# OTGW01_opentherm_rev1.net
KiCad netlist of a schematic drawn in Altium Designer
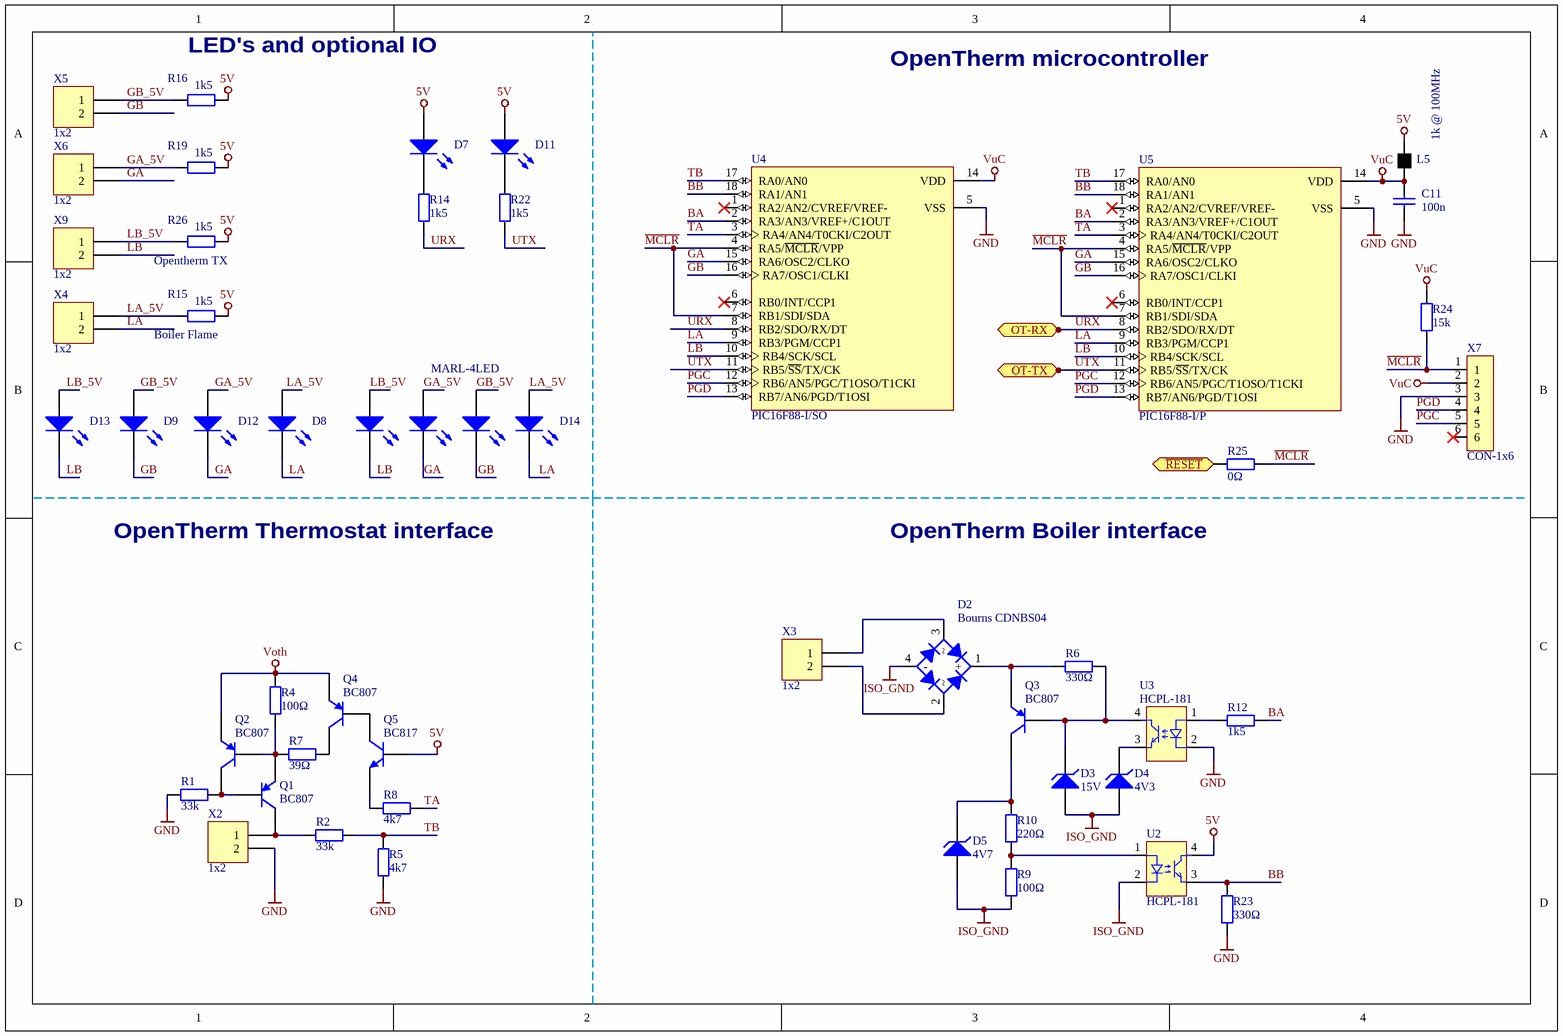
[diagram p0: OTGW01_opentherm_rev1.SchDoc]

(export (version "E")
  (design (tool "Eeschema 10.0.6"))
  (components
    (comp (ref "C11")
      (value "100n")
      (footprint "0805")
      (description "Capacitor Non Polarized")
      (libsource (lib "sap") (part "C"))
    )
    (comp (ref "D2")
      (value "Bourns CDNBS04")
      (footprint "SOD-106")
      (description "Full Wave Diode Bridge")
      (libsource (lib "OTGW01_rev1") (part "Bridge"))
    )
    (comp (ref "D3")
      (value "15V")
      (footprint "SOD123")
      (description "Zener Diode")
      (libsource (lib "OTGW01_rev1") (part "D_Z"))
    )
    (comp (ref "D4")
      (value "4V3")
      (footprint "SOD123")
      (description "Zener Diode")
      (libsource (lib "OTGW01_rev1") (part "D_Z"))
    )
    (comp (ref "D5")
      (value "4V7")
      (footprint "SOD123")
      (description "Zener Diode")
      (libsource (lib "OTGW01_rev1") (part "D_Z"))
    )
    (comp (ref "D7")
      (value "PLCC2 LED")
      (footprint "PLCC2")
      (description "LED")
      (libsource (lib "OTGW01_rev1") (part "LED"))
    )
    (comp (ref "D8")
      (value "PLCC2 LED")
      (footprint "PLCC2")
      (description "LED")
      (libsource (lib "OTGW01_rev1") (part "LED"))
    )
    (comp (ref "D9")
      (value "PLCC2 LED")
      (footprint "PLCC2")
      (description "LED")
      (libsource (lib "OTGW01_rev1") (part "LED"))
    )
    (comp (ref "D11")
      (value "PLCC2 LED")
      (footprint "PLCC2")
      (description "LED")
      (libsource (lib "OTGW01_rev1") (part "LED"))
    )
    (comp (ref "D12")
      (value "PLCC2 LED")
      (footprint "PLCC2")
      (description "LED")
      (libsource (lib "OTGW01_rev1") (part "LED"))
    )
    (comp (ref "D13")
      (value "PLCC2 LED")
      (footprint "PLCC2")
      (description "LED")
      (libsource (lib "OTGW01_rev1") (part "LED"))
    )
    (comp (ref "D14")
      (value "MARL-4LED")
      (footprint "MARL-4LED")
      (libsource (lib "OTGW01_rev1") (part "MARL-4LED"))
    )
    (comp (ref "L5")
      (value "1k @ 100MHz")
      (footprint "0805")
      (libsource (lib "OTGW01_rev1") (part "Ferrite"))
    )
    (comp (ref "Q1")
      (value "BC807")
      (footprint "SOT23")
      (description "PNP Medium Power Transistor")
      (libsource (lib "OTGW01_rev1") (part "PNP"))
    )
    (comp (ref "Q2")
      (value "BC807")
      (footprint "SOT23")
      (description "PNP Medium Power Transistor")
      (libsource (lib "OTGW01_rev1") (part "PNP"))
    )
    (comp (ref "Q3")
      (value "BC807")
      (footprint "SOT23")
      (description "PNP Medium Power Transistor")
      (libsource (lib "OTGW01_rev1") (part "PNP"))
    )
    (comp (ref "Q4")
      (value "BC807")
      (footprint "SOT23")
      (description "PNP Medium Power Transistor")
      (libsource (lib "OTGW01_rev1") (part "PNP"))
    )
    (comp (ref "Q5")
      (value "BC817")
      (footprint "SOT23")
      (description "NPN Medium Power Transistor")
      (libsource (lib "OTGW01_rev1") (part "NPN"))
    )
    (comp (ref "R1")
      (value "33k")
      (footprint "0805")
      (description "Resistor")
      (libsource (lib "OTGW01_rev1") (part "R"))
    )
    (comp (ref "R2")
      (value "33k")
      (footprint "0805")
      (description "Resistor")
      (libsource (lib "OTGW01_rev1") (part "R"))
    )
    (comp (ref "R4")
      (value "100Ω")
      (footprint "0805")
      (description "Resistor")
      (libsource (lib "") (part "R_2"))
    )
    (comp (ref "R5")
      (value "4k7")
      (footprint "0805")
      (description "Resistor")
      (libsource (lib "") (part "R_2"))
    )
    (comp (ref "R6")
      (value "330Ω")
      (footprint "0805")
      (description "Resistor")
      (libsource (lib "") (part "R_3"))
    )
    (comp (ref "R7")
      (value "39Ω")
      (footprint "0805")
      (description "Resistor")
      (libsource (lib "OTGW01_rev1") (part "R"))
    )
    (comp (ref "R8")
      (value "4k7")
      (footprint "0805")
      (description "Resistor")
      (libsource (lib "OTGW01_rev1") (part "R"))
    )
    (comp (ref "R9")
      (value "100Ω")
      (footprint "0805")
      (description "Resistor")
      (libsource (lib "") (part "R_1"))
    )
    (comp (ref "R10")
      (value "220Ω")
      (footprint "0805")
      (description "Resistor")
      (libsource (lib "") (part "R_1"))
    )
    (comp (ref "R12")
      (value "1k5")
      (footprint "0805")
      (description "Resistor")
      (libsource (lib "") (part "R_3"))
    )
    (comp (ref "R14")
      (value "1k5")
      (footprint "0805")
      (description "Resistor")
      (libsource (lib "") (part "R_2"))
    )
    (comp (ref "R15")
      (value "1k5")
      (footprint "0805")
      (description "Resistor")
      (libsource (lib "OTGW01_rev1") (part "R"))
    )
    (comp (ref "R16")
      (value "1k5")
      (footprint "0805")
      (description "Resistor")
      (libsource (lib "OTGW01_rev1") (part "R"))
    )
    (comp (ref "R19")
      (value "1k5")
      (footprint "0805")
      (description "Resistor")
      (libsource (lib "OTGW01_rev1") (part "R"))
    )
    (comp (ref "R22")
      (value "1k5")
      (footprint "0805")
      (description "Resistor")
      (libsource (lib "") (part "R_2"))
    )
    (comp (ref "R23")
      (value "330Ω")
      (footprint "0805")
      (description "Resistor")
      (libsource (lib "") (part "R_1"))
    )
    (comp (ref "R24")
      (value "15k")
      (footprint "0805")
      (description "Resistor")
      (libsource (lib "") (part "R_1"))
    )
    (comp (ref "R25")
      (value "0Ω")
      (footprint "0805")
      (description "Resistor")
      (libsource (lib "OTGW01_rev1") (part "R"))
    )
    (comp (ref "R26")
      (value "1k5")
      (footprint "0805")
      (description "Resistor")
      (libsource (lib "OTGW01_rev1") (part "R"))
    )
    (comp (ref "U2")
      (value "HCPL-181")
      (footprint "HCPL-181")
      (libsource (lib "OTGW01_rev1") (part "HCPL-181"))
    )
    (comp (ref "U3") (value "HCPL-181") (footprint "HCPL-181") (libsource (lib "") (part "HCPL-181_1")))
    (comp (ref "U4")
      (value "PIC16F88-I/SO")
      (footprint "SOIC18")
      (libsource (lib "OTGW01_rev1") (part "MC-8B-16F88-IL18"))
    )
    (comp (ref "U5")
      (value "PIC16F88-I/P")
      (footprint "PDIP300-P18")
      (libsource (lib "OTGW01_rev1") (part "MC-8B-16F88-IL18"))
    )
    (comp (ref "X2")
      (value "1x2")
      (footprint "Terminal_2x3.5mm")
      (libsource (lib "OTGW01_rev1") (part "CON_1x2"))
    )
    (comp (ref "X3")
      (value "1x2")
      (footprint "Terminal_2x3.5mm")
      (libsource (lib "OTGW01_rev1") (part "CON_1x2"))
    )
    (comp (ref "X4")
      (value "1x2")
      (footprint "Terminal_2x3.5mm")
      (libsource (lib "OTGW01_rev1") (part "CON_1x2"))
    )
    (comp (ref "X5")
      (value "1x2")
      (footprint "Terminal_2x3.5mm")
      (libsource (lib "OTGW01_rev1") (part "CON_1x2"))
    )
    (comp (ref "X6")
      (value "1x2")
      (footprint "Terminal_2x3.5mm")
      (libsource (lib "OTGW01_rev1") (part "CON_1x2"))
    )
    (comp (ref "X7")
      (value "CON-1x6")
      (footprint "SIL-1x6-2.54")
      (libsource (lib "OTGW01_rev1") (part "CON-1x6"))
    )
    (comp (ref "X9")
      (value "1x2")
      (footprint "Terminal_2x3.5mm")
      (libsource (lib "OTGW01_rev1") (part "CON_1x2"))
    )
  )
  (nets
    (net (code "1") (name "/BA") (class "Default")
      (node (ref "R12") (pin "1") (pinfunction "1_1") (pintype "passive"))
      (node (ref "U4") (pin "2") (pinfunction "RA3/AN3/VREF+/C1OUT_2") (pintype "bidirectional"))
      (node (ref "U5") (pin "2") (pinfunction "RA3/AN3/VREF+/C1OUT_2") (pintype "bidirectional"))
    )
    (net (code "2") (name "/BB") (class "Default")
      (node (ref "R23") (pin "1") (pinfunction "1_1") (pintype "passive"))
      (node (ref "U2") (pin "3") (pinfunction "C_3") (pintype "passive"))
      (node (ref "U4") (pin "18") (pinfunction "RA1/AN1_18") (pintype "bidirectional"))
      (node (ref "U5") (pin "18") (pinfunction "RA1/AN1_18") (pintype "bidirectional"))
    )
    (net (code "3") (name "/GA") (class "Default")
      (node (ref "D12") (pin "2") (pinfunction "K_2") (pintype "passive"))
      (node (ref "D14") (pin "6") (pinfunction "K_6") (pintype "passive"))
      (node (ref "U4") (pin "15") (pinfunction "RA6/OSC2/CLKO_15") (pintype "bidirectional"))
      (node (ref "U5") (pin "15") (pinfunction "RA6/OSC2/CLKO_15") (pintype "bidirectional"))
      (node (ref "X6") (pin "2") (pinfunction "2_2") (pintype "passive"))
    )
    (net (code "4") (name "/GA_5V") (class "Default")
      (node (ref "D12") (pin "1") (pinfunction "A_1") (pintype "passive"))
      (node (ref "D14") (pin "5") (pinfunction "A_5") (pintype "passive"))
      (node (ref "R19") (pin "1") (pinfunction "1_1") (pintype "passive"))
      (node (ref "X6") (pin "1") (pinfunction "1_1") (pintype "passive"))
    )
    (net (code "5") (name "/GB") (class "Default")
      (node (ref "D14") (pin "4") (pinfunction "K_4") (pintype "passive"))
      (node (ref "D9") (pin "2") (pinfunction "K_2") (pintype "passive"))
      (node (ref "U4") (pin "16") (pinfunction "RA7/OSC1/CLKI_16") (pintype "bidirectional"))
      (node (ref "U5") (pin "16") (pinfunction "RA7/OSC1/CLKI_16") (pintype "bidirectional"))
      (node (ref "X5") (pin "2") (pinfunction "2_2") (pintype "passive"))
    )
    (net (code "6") (name "/GB_5V") (class "Default")
      (node (ref "D14") (pin "3") (pinfunction "A_3") (pintype "passive"))
      (node (ref "D9") (pin "1") (pinfunction "A_1") (pintype "passive"))
      (node (ref "R16") (pin "1") (pinfunction "1_1") (pintype "passive"))
      (node (ref "X5") (pin "1") (pinfunction "1_1") (pintype "passive"))
    )
    (net (code "7") (name "/LA") (class "Default")
      (node (ref "D14") (pin "2") (pinfunction "K_2") (pintype "passive"))
      (node (ref "D8") (pin "2") (pinfunction "K_2") (pintype "passive"))
      (node (ref "U4") (pin "9") (pinfunction "RB3/PGM/CCP1_9") (pintype "bidirectional"))
      (node (ref "U5") (pin "9") (pinfunction "RB3/PGM/CCP1_9") (pintype "bidirectional"))
      (node (ref "X4") (pin "2") (pinfunction "2_2") (pintype "passive"))
    )
    (net (code "8") (name "/LA_5V") (class "Default")
      (node (ref "D14") (pin "1") (pinfunction "A_1") (pintype "passive"))
      (node (ref "D8") (pin "1") (pinfunction "A_1") (pintype "passive"))
      (node (ref "R15") (pin "1") (pinfunction "1_1") (pintype "passive"))
      (node (ref "X4") (pin "1") (pinfunction "1_1") (pintype "passive"))
    )
    (net (code "9") (name "/LB") (class "Default")
      (node (ref "D13") (pin "2") (pinfunction "K_2") (pintype "passive"))
      (node (ref "D14") (pin "8") (pinfunction "K_8") (pintype "passive"))
      (node (ref "U4") (pin "10") (pinfunction "RB4/SCK/SCL_10") (pintype "bidirectional"))
      (node (ref "U5") (pin "10") (pinfunction "RB4/SCK/SCL_10") (pintype "bidirectional"))
      (node (ref "X9") (pin "2") (pinfunction "2_2") (pintype "passive"))
    )
    (net (code "10") (name "/LB_5V") (class "Default")
      (node (ref "D13") (pin "1") (pinfunction "A_1") (pintype "passive"))
      (node (ref "D14") (pin "7") (pinfunction "A_7") (pintype "passive"))
      (node (ref "R26") (pin "1") (pinfunction "1_1") (pintype "passive"))
      (node (ref "X9") (pin "1") (pinfunction "1_1") (pintype "passive"))
    )
    (net (code "11") (name "/PGC") (class "Default")
      (node (ref "U4") (pin "12") (pinfunction "RB6/AN5/PGC/T1OSO/T1CKI_12") (pintype "bidirectional"))
      (node (ref "U5") (pin "12") (pinfunction "RB6/AN5/PGC/T1OSO/T1CKI_12") (pintype "bidirectional"))
      (node (ref "X7") (pin "5") (pinfunction "5_5") (pintype "passive"))
    )
    (net (code "12") (name "/PGD") (class "Default")
      (node (ref "U4") (pin "13") (pinfunction "RB7/AN6/PGD/T1OSI_13") (pintype "bidirectional"))
      (node (ref "U5") (pin "13") (pinfunction "RB7/AN6/PGD/T1OSI_13") (pintype "bidirectional"))
      (node (ref "X7") (pin "4") (pinfunction "4_4") (pintype "passive"))
    )
    (net (code "13") (name "/TA") (class "Default")
      (node (ref "R8") (pin "2") (pinfunction "2_2") (pintype "passive"))
      (node (ref "U4") (pin "3") (pinfunction "RA4/AN4/T0CKI/C2OUT_3") (pintype "bidirectional"))
      (node (ref "U5") (pin "3") (pinfunction "RA4/AN4/T0CKI/C2OUT_3") (pintype "bidirectional"))
    )
    (net (code "14") (name "/TB") (class "Default")
      (node (ref "R2") (pin "2") (pinfunction "2_2") (pintype "passive"))
      (node (ref "R5") (pin "2") (pinfunction "2_2") (pintype "passive"))
      (node (ref "U4") (pin "17") (pinfunction "RA0/AN0_17") (pintype "bidirectional"))
      (node (ref "U5") (pin "17") (pinfunction "RA0/AN0_17") (pintype "bidirectional"))
    )
    (net (code "15") (name "/URX") (class "Default")
      (node (ref "R14") (pin "1") (pinfunction "1_1") (pintype "passive"))
      (node (ref "U4") (pin "8") (pinfunction "RB2/SDO/RX/DT_8") (pintype "bidirectional"))
      (node (ref "U5") (pin "8") (pinfunction "RB2/SDO/RX/DT_8") (pintype "bidirectional"))
    )
    (net (code "16") (name "/UTX") (class "Default")
      (node (ref "R22") (pin "1") (pinfunction "1_1") (pintype "passive"))
      (node (ref "U4") (pin "11") (pinfunction "RB5/~{SS}/TX/CK_11") (pintype "bidirectional"))
      (node (ref "U5") (pin "11") (pinfunction "RB5/~{SS}/TX/CK_11") (pintype "bidirectional"))
    )
    (net (code "17") (name "/~{MCLR}") (class "Default")
      (node (ref "R24") (pin "2") (pinfunction "2_2") (pintype "passive"))
      (node (ref "R25") (pin "2") (pinfunction "2_2") (pintype "passive"))
      (node (ref "U4") (pin "4") (pinfunction "RA5/~{MCLR}/VPP_4") (pintype "bidirectional"))
      (node (ref "U4") (pin "7") (pinfunction "RB1/SDI/SDA_7") (pintype "bidirectional"))
      (node (ref "U5") (pin "4") (pinfunction "RA5/~{MCLR}/VPP_4") (pintype "bidirectional"))
      (node (ref "U5") (pin "7") (pinfunction "RB1/SDI/SDA_7") (pintype "bidirectional"))
      (node (ref "X7") (pin "1") (pinfunction "1_1") (pintype "passive"))
    )
    (net (code "18") (name "/~{RESET}") (class "Default")
      (node (ref "R25") (pin "1") (pinfunction "1_1") (pintype "passive"))
    )
    (net (code "19") (name "5V") (class "Default")
      (node (ref "D11") (pin "1") (pinfunction "A_1") (pintype "passive"))
      (node (ref "D7") (pin "1") (pinfunction "A_1") (pintype "passive"))
      (node (ref "L5") (pin "2") (pinfunction "OUT_2") (pintype "passive"))
      (node (ref "Q5") (pin "3") (pinfunction "B_3") (pintype "passive"))
      (node (ref "R15") (pin "2") (pinfunction "2_2") (pintype "passive"))
      (node (ref "R16") (pin "2") (pinfunction "2_2") (pintype "passive"))
      (node (ref "R19") (pin "2") (pinfunction "2_2") (pintype "passive"))
      (node (ref "R26") (pin "2") (pinfunction "2_2") (pintype "passive"))
      (node (ref "U2") (pin "4") (pinfunction "D_4") (pintype "passive"))
    )
    (net (code "20") (name "GND") (class "Default")
      (node (ref "C11") (pin "1") (pinfunction "1_1") (pintype "passive"))
      (node (ref "R1") (pin "1") (pinfunction "1_1") (pintype "passive"))
      (node (ref "R23") (pin "2") (pinfunction "2_2") (pintype "passive"))
      (node (ref "R5") (pin "1") (pinfunction "1_1") (pintype "passive"))
      (node (ref "U3") (pin "2") (pinfunction "B_2") (pintype "passive"))
      (node (ref "U4") (pin "5") (pinfunction "VSS_5") (pintype "power_in"))
      (node (ref "U5") (pin "5") (pinfunction "VSS_5") (pintype "power_in"))
      (node (ref "X2") (pin "2") (pinfunction "2_2") (pintype "passive"))
      (node (ref "X7") (pin "3") (pinfunction "3_3") (pintype "passive"))
    )
    (net (code "21") (name "ISO_GND") (class "Default")
      (node (ref "D2") (pin "4") (pinfunction "-_4") (pintype "passive"))
      (node (ref "D3") (pin "2") (pinfunction "Anode_2") (pintype "passive"))
      (node (ref "D4") (pin "2") (pinfunction "Anode_2") (pintype "passive"))
      (node (ref "D5") (pin "2") (pinfunction "Anode_2") (pintype "passive"))
      (node (ref "R9") (pin "2") (pinfunction "2_2") (pintype "passive"))
      (node (ref "U2") (pin "2") (pinfunction "B_2") (pintype "passive"))
    )
    (net (code "22") (name "Net-(D2-+)") (class "Default")
      (node (ref "D2") (pin "1") (pinfunction "+_1") (pintype "passive"))
      (node (ref "Q3") (pin "2") (pinfunction "E_2") (pintype "passive"))
      (node (ref "R6") (pin "2") (pinfunction "2_2") (pintype "passive"))
    )
    (net (code "23") (name "Net-(D2-~-Pad2)") (class "Default")
      (node (ref "D2") (pin "2") (pinfunction "~_2") (pintype "passive"))
      (node (ref "X3") (pin "2") (pinfunction "2_2") (pintype "passive"))
    )
    (net (code "24") (name "Net-(D2-~-Pad3)") (class "Default")
      (node (ref "D2") (pin "3") (pinfunction "~_3") (pintype "passive"))
      (node (ref "X3") (pin "1") (pinfunction "1_1") (pintype "passive"))
    )
    (net (code "25") (name "Net-(D3-Cathode)") (class "Default")
      (node (ref "D3") (pin "1") (pinfunction "Cathode_1") (pintype "passive"))
      (node (ref "Q3") (pin "1") (pinfunction "B_1") (pintype "passive"))
      (node (ref "R6") (pin "1") (pinfunction "1_1") (pintype "passive"))
      (node (ref "U3") (pin "4") (pinfunction "D_4") (pintype "passive"))
    )
    (net (code "26") (name "Net-(D4-Cathode)") (class "Default")
      (node (ref "D4") (pin "1") (pinfunction "Cathode_1") (pintype "passive"))
      (node (ref "U3") (pin "3") (pinfunction "C_3") (pintype "passive"))
    )
    (net (code "27") (name "Net-(D5-Cathode)") (class "Default")
      (node (ref "D5") (pin "1") (pinfunction "Cathode_1") (pintype "passive"))
      (node (ref "Q3") (pin "3") (pinfunction "C_3") (pintype "passive"))
      (node (ref "R10") (pin "1") (pinfunction "1_1") (pintype "passive"))
    )
    (net (code "28") (name "Net-(D7-K)") (class "Default")
      (node (ref "D7") (pin "2") (pinfunction "K_2") (pintype "passive"))
      (node (ref "R14") (pin "2") (pinfunction "2_2") (pintype "passive"))
    )
    (net (code "29") (name "Net-(D11-K)") (class "Default")
      (node (ref "D11") (pin "2") (pinfunction "K_2") (pintype "passive"))
      (node (ref "R22") (pin "2") (pinfunction "2_2") (pintype "passive"))
    )
    (net (code "30") (name "Net-(Q1-B)") (class "Default")
      (node (ref "Q1") (pin "1") (pinfunction "B_1") (pintype "passive"))
      (node (ref "Q2") (pin "3") (pinfunction "C_3") (pintype "passive"))
      (node (ref "R1") (pin "2") (pinfunction "2_2") (pintype "passive"))
    )
    (net (code "31") (name "Net-(Q1-C)") (class "Default")
      (node (ref "Q1") (pin "3") (pinfunction "C_3") (pintype "passive"))
      (node (ref "R2") (pin "1") (pinfunction "1_1") (pintype "passive"))
      (node (ref "X2") (pin "1") (pinfunction "1_1") (pintype "passive"))
    )
    (net (code "32") (name "Net-(Q1-E)") (class "Default")
      (node (ref "Q1") (pin "2") (pinfunction "E_2") (pintype "passive"))
      (node (ref "Q2") (pin "1") (pinfunction "B_1") (pintype "passive"))
      (node (ref "R4") (pin "1") (pinfunction "1_1") (pintype "passive"))
      (node (ref "R7") (pin "1") (pinfunction "1_1") (pintype "passive"))
    )
    (net (code "33") (name "Net-(Q4-B)") (class "Default")
      (node (ref "Q4") (pin "1") (pinfunction "B_1") (pintype "passive"))
      (node (ref "Q5") (pin "2") (pinfunction "C_2") (pintype "passive"))
    )
    (net (code "34") (name "Net-(Q4-C)") (class "Default")
      (node (ref "Q4") (pin "3") (pinfunction "C_3") (pintype "passive"))
      (node (ref "R7") (pin "2") (pinfunction "2_2") (pintype "passive"))
    )
    (net (code "35") (name "Net-(Q5-E)") (class "Default")
      (node (ref "Q5") (pin "1") (pinfunction "E_1") (pintype "passive"))
      (node (ref "R8") (pin "1") (pinfunction "1_1") (pintype "passive"))
    )
    (net (code "36") (name "Net-(U2-A)") (class "Default")
      (node (ref "R10") (pin "2") (pinfunction "2_2") (pintype "passive"))
      (node (ref "R9") (pin "1") (pinfunction "1_1") (pintype "passive"))
      (node (ref "U2") (pin "1") (pinfunction "A_1") (pintype "passive"))
    )
    (net (code "37") (name "Net-(U3-A)") (class "Default")
      (node (ref "R12") (pin "2") (pinfunction "2_2") (pintype "passive"))
      (node (ref "U3") (pin "1") (pinfunction "A_1") (pintype "passive"))
    )
    (net (code "38") (name "Voth") (class "Default")
      (node (ref "Q2") (pin "2") (pinfunction "E_2") (pintype "passive"))
      (node (ref "Q4") (pin "2") (pinfunction "E_2") (pintype "passive"))
      (node (ref "R4") (pin "2") (pinfunction "2_2") (pintype "passive"))
    )
    (net (code "39") (name "VuC") (class "Default")
      (node (ref "C11") (pin "2") (pinfunction "2_2") (pintype "passive"))
      (node (ref "L5") (pin "1") (pinfunction "IN_1") (pintype "passive"))
      (node (ref "R24") (pin "1") (pinfunction "1_1") (pintype "passive"))
      (node (ref "U4") (pin "14") (pinfunction "VDD_14") (pintype "power_in"))
      (node (ref "U5") (pin "14") (pinfunction "VDD_14") (pintype "power_in"))
      (node (ref "X7") (pin "2") (pinfunction "2_2") (pintype "passive"))
    )
    (net (code "40") (name "unconnected-(U4-RA2{slash}AN2{slash}CVREF{slash}VREF--Pad1)") (class "Default")
      (node (ref "U4") (pin "1") (pinfunction "RA2/AN2/CVREF/VREF-_1") (pintype "bidirectional+no_connect"))
    )
    (net (code "41") (name "unconnected-(U4-RB0{slash}INT{slash}CCP1-Pad6)") (class "Default")
      (node (ref "U4") (pin "6") (pinfunction "RB0/INT/CCP1_6") (pintype "bidirectional+no_connect"))
    )
    (net (code "42") (name "unconnected-(U5-RA2{slash}AN2{slash}CVREF{slash}VREF--Pad1)") (class "Default")
      (node (ref "U5") (pin "1") (pinfunction "RA2/AN2/CVREF/VREF-_1") (pintype "bidirectional+no_connect"))
    )
    (net (code "43") (name "unconnected-(U5-RB0{slash}INT{slash}CCP1-Pad6)") (class "Default")
      (node (ref "U5") (pin "6") (pinfunction "RB0/INT/CCP1_6") (pintype "bidirectional+no_connect"))
    )
    (net (code "44") (name "unconnected-(X7-Pad6)") (class "Default")
      (node (ref "X7") (pin "6") (pinfunction "6_6") (pintype "passive+no_connect"))
    )
  )
)
